# BLE_SCH_Rev1.net
KiCad netlist of a schematic drawn in Altium Designer
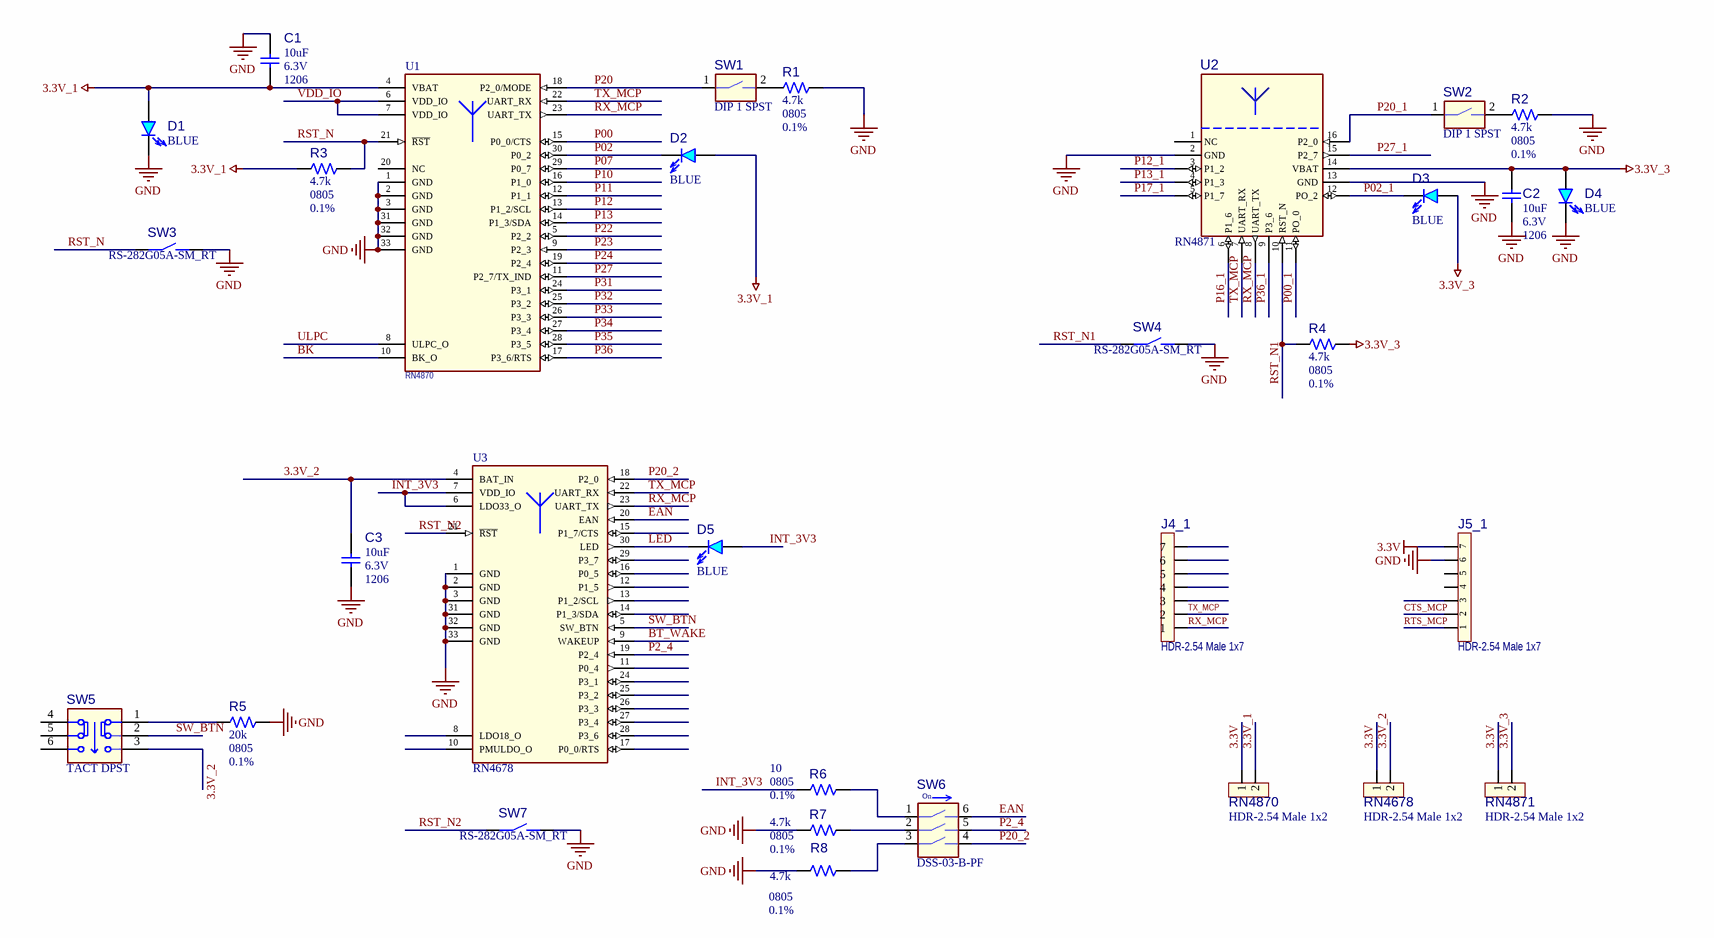
[diagram p0: BLE_SCH_Rev1.SchDoc]

(export (version "E")
  (design (tool "Eeschema 10.0.6"))
  (components
    (comp (ref "C1")
      (value "10uF")
      (footprint "CAP_C_1206")
      (fields
        (field (name "VOLTAGE") "6.3V")
        (field (name "PACKAGE") "1206")
        (field (name "TOLERANCE") "20%")
        (field (name "Comment") "Capacitor NP")
      )
      (libsource (lib "MCHP-CDB") (part "Capacitor NP"))
    )
    (comp (ref "C2")
      (value "10uF")
      (footprint "CAP_C_1206")
      (fields
        (field (name "VOLTAGE") "6.3V")
        (field (name "PACKAGE") "1206")
        (field (name "TOLERANCE") "20%")
        (field (name "Comment") "Capacitor NP")
      )
      (libsource (lib "MCHP-CDB") (part "Capacitor NP"))
    )
    (comp (ref "C3")
      (value "10uF")
      (footprint "CAP_C_1206")
      (fields
        (field (name "VOLTAGE") "6.3V")
        (field (name "PACKAGE") "1206")
        (field (name "TOLERANCE") "20%")
        (field (name "Comment") "Capacitor NP")
      )
      (libsource (lib "MCHP-CDB") (part "Capacitor NP"))
    )
    (comp (ref "D1")
      (value "BLUE")
      (footprint "LED_0805_BLUE")
      (description "LED")
      (fields (field (name "Comment") "LED_blue"))
      (libsource (lib "MCHP-CDB") (part "LED_blue"))
    )
    (comp (ref "D2")
      (value "BLUE")
      (footprint "LED_0805_BLUE")
      (description "LED")
      (fields (field (name "Comment") "LED_blue"))
      (libsource (lib "MCHP-CDB") (part "LED_blue"))
    )
    (comp (ref "D3")
      (value "BLUE")
      (footprint "LED_0805_BLUE")
      (description "LED")
      (fields (field (name "Comment") "LED_blue"))
      (libsource (lib "MCHP-CDB") (part "LED_blue"))
    )
    (comp (ref "D4")
      (value "BLUE")
      (footprint "LED_0805_BLUE")
      (description "LED")
      (fields (field (name "Comment") "LED_blue"))
      (libsource (lib "MCHP-CDB") (part "LED_blue"))
    )
    (comp (ref "D5")
      (value "BLUE")
      (footprint "LED_0805_BLUE")
      (description "LED")
      (fields (field (name "Comment") "LED_blue"))
      (libsource (lib "MCHP-CDB") (part "LED_blue"))
    )
    (comp (ref "J4_1")
      (value "HDR-2.54 Male 1x7")
      (footprint "HDR_M_2.54_1x7")
      (fields (field (name "Comment") "Header 1x7"))
      (libsource (lib "MCHP-CDB") (part "Header 1x7"))
    )
    (comp (ref "J5_1")
      (value "HDR-2.54 Male 1x7")
      (footprint "HDR_M_2.54_1x7")
      (fields (field (name "Comment") "Header 1x7"))
      (libsource (lib "") (part "Header 1x7_1"))
    )
    (comp (ref "R1")
      (value "4.7k")
      (footprint "RES_C_0805")
      (description "Resistor")
      (fields (field (name "PACKAGE") "0805") (field (name "TOLERANCE") "0.1%"))
      (libsource (lib "MCHP-CDB") (part "Resistor"))
    )
    (comp (ref "R2")
      (value "4.7k")
      (footprint "RES_C_0805")
      (description "Resistor")
      (fields (field (name "PACKAGE") "0805") (field (name "TOLERANCE") "0.1%"))
      (libsource (lib "MCHP-CDB") (part "Resistor"))
    )
    (comp (ref "R3")
      (value "4.7k")
      (footprint "RES_C_0805")
      (description "Resistor")
      (fields (field (name "PACKAGE") "0805") (field (name "TOLERANCE") "0.1%"))
      (libsource (lib "MCHP-CDB") (part "Resistor"))
    )
    (comp (ref "R4")
      (value "4.7k")
      (footprint "RES_C_0805")
      (description "Resistor")
      (fields (field (name "PACKAGE") "0805") (field (name "TOLERANCE") "0.1%"))
      (libsource (lib "MCHP-CDB") (part "Resistor"))
    )
    (comp (ref "R5")
      (value "20k")
      (footprint "RES_C_0805")
      (description "Resistor")
      (fields (field (name "PACKAGE") "0805") (field (name "TOLERANCE") "0.1%"))
      (libsource (lib "MCHP-CDB") (part "Resistor"))
    )
    (comp (ref "R6")
      (value "10")
      (footprint "RES_C_0805")
      (description "Resistor")
      (fields (field (name "PACKAGE") "0805") (field (name "TOLERANCE") "0.1%"))
      (libsource (lib "MCHP-CDB") (part "Resistor"))
    )
    (comp (ref "R7")
      (value "4.7k")
      (footprint "RES_C_0805")
      (description "Resistor")
      (fields (field (name "PACKAGE") "0805") (field (name "TOLERANCE") "0.1%"))
      (libsource (lib "MCHP-CDB") (part "Resistor"))
    )
    (comp (ref "R8")
      (value "4.7k")
      (footprint "RES_C_0805")
      (description "Resistor")
      (fields (field (name "PACKAGE") "0805") (field (name "TOLERANCE") "0.1%"))
      (libsource (lib "MCHP-CDB") (part "Resistor"))
    )
    (comp (ref "RN4678")
      (value "HDR-2.54 Male 1x2")
      (footprint "HDR_M_2.54_1x2")
      (fields (field (name "Comment") "Header 1x2") (field (name "OWNER") "Randolph Sobrepena"))
      (libsource (lib "MCHP-CDB") (part "Header 1x2"))
    )
    (comp (ref "RN4870")
      (value "HDR-2.54 Male 1x2")
      (footprint "HDR_M_2.54_1x2")
      (fields (field (name "Comment") "Header 1x2") (field (name "OWNER") "Randolph Sobrepena"))
      (libsource (lib "MCHP-CDB") (part "Header 1x2"))
    )
    (comp (ref "RN4871")
      (value "HDR-2.54 Male 1x2")
      (footprint "HDR_M_2.54_1x2")
      (fields (field (name "Comment") "Header 1x2") (field (name "OWNER") "Randolph Sobrepena"))
      (libsource (lib "MCHP-CDB") (part "Header 1x2"))
    )
    (comp (ref "SW1")
      (value "DIP 1 SPST")
      (footprint "SW_TH_2.54MM X 1 418117270901")
      (description "Switch DIP 1 Pos")
      (fields (field (name "VOLTAGE") "24V") (field (name "OWNER") "Gabor Bihari"))
      (libsource (lib "MCHP-CDB") (part "Switch DIP 1 Pos"))
    )
    (comp (ref "SW2")
      (value "DIP 1 SPST")
      (footprint "SW_TH_2.54MM X 1 418117270901")
      (description "Switch DIP 1 Pos")
      (fields (field (name "VOLTAGE") "24V") (field (name "OWNER") "Gabor Bihari"))
      (libsource (lib "MCHP-CDB") (part "Switch DIP 1 Pos"))
    )
    (comp (ref "SW3")
      (value "RS-282G05A-SM_RT")
      (footprint "SW_TACT_SMD_CK_RS-282G05A3-SM RT")
      (description "Switch")
      (fields
        (field (name "VOLTAGE") "12V")
        (field (name "Comment") "Switch 2 Pin")
        (field (name "OWNER") "Gabor Bihari")
      )
      (libsource (lib "MCHP-CDB") (part "Switch 2 Pin"))
    )
    (comp (ref "SW4")
      (value "RS-282G05A-SM_RT")
      (footprint "SW_TACT_SMD_CK_RS-282G05A3-SM RT")
      (description "Switch")
      (fields
        (field (name "VOLTAGE") "12V")
        (field (name "Comment") "Switch 2 Pin")
        (field (name "OWNER") "Gabor Bihari")
      )
      (libsource (lib "MCHP-CDB") (part "Switch 2 Pin"))
    )
    (comp (ref "SW5")
      (value "TACT DPST")
      (footprint "SW_TACT_TH_PS07-22L-PF")
      (description "PS-5177")
      (fields (field (name "Comment") "Switch on-off 6 Pin") (field (name "OWNER") "Duane Burt"))
      (libsource (lib "MCHP-CDB") (part "Switch on-off 6 Pin"))
    )
    (comp (ref "SW6")
      (value "DSS-03-B-PF")
      (footprint "SW_TH_2.54MM X 3 Omron")
      (description "Switch DIP")
      (fields (field (name "Comment") "Switch DIP 3 Pos") (field (name "OWNER") "Duane Burt"))
      (libsource (lib "MCHP-CDB") (part "Switch DIP 3 Pos"))
    )
    (comp (ref "SW7")
      (value "RS-282G05A-SM_RT")
      (footprint "SW_TACT_SMD_CK_RS-282G05A3-SM RT")
      (description "Switch")
      (fields
        (field (name "VOLTAGE") "12V")
        (field (name "Comment") "Switch 2 Pin")
        (field (name "OWNER") "Gabor Bihari")
      )
      (libsource (lib "MCHP-CDB") (part "Switch 2 Pin"))
    )
    (comp (ref "U1")
      (value "RN4870")
      (footprint "MOD_BM70BLES1FC2")
      (fields (field (name "Comment") "MODULE BM70BLES1FC2") (field (name "OWNER") "Jojie Batislaon"))
      (libsource (lib "MCHP-CDB") (part "MODULE BM70BLES1FC2"))
    )
    (comp (ref "U2")
      (value "RN4871")
      (footprint "RN4871 MODULE-16")
      (fields (field (name "Comment") "RN4871 MODULE") (field (name "OWNER") "Octavian Stroe"))
      (libsource (lib "MCHP-CDB") (part "RN4871 MODULE"))
    )
    (comp (ref "U3")
      (value "RN4678")
      (footprint "MOD_BM78SPPS5xC2")
      (fields (field (name "Comment") "MODULE BM78SPPS5xC2") (field (name "OWNER") "Jojie Batislaon"))
      (libsource (lib "MCHP-CDB") (part "MODULE BM78SPPS5xC2"))
    )
  )
  (nets
    (net (code "1") (name "/3.3V_2") (class "Default")
      (node (ref "C3") (pin "2") (pinfunction "2_2") (pintype "passive"))
      (node (ref "RN4678") (pin "2") (pinfunction "2_2") (pintype "passive"))
      (node (ref "SW5") (pin "3") (pinfunction "3_3") (pintype "passive"))
      (node (ref "U3") (pin "4") (pinfunction "BAT_IN_4") (pintype "power_in"))
    )
    (net (code "2") (name "/BK") (class "Default")
      (node (ref "U1") (pin "10") (pinfunction "BK_O_10") (pintype "passive"))
    )
    (net (code "3") (name "/BT_WAKE") (class "Default")
      (node (ref "U3") (pin "9") (pinfunction "WAKEUP_9") (pintype "input"))
    )
    (net (code "4") (name "/CTS_MCP") (class "Default")
      (node (ref "J5_1") (pin "2") (pinfunction "2_2") (pintype "passive"))
    )
    (net (code "5") (name "/EAN") (class "Default")
      (node (ref "SW6") (pin "6") (pinfunction "6_6") (pintype "passive"))
      (node (ref "U3") (pin "20") (pinfunction "EAN_20") (pintype "input"))
    )
    (net (code "6") (name "/INT_3V3") (class "Default")
      (node (ref "D5") (pin "1") (pinfunction "A_1") (pintype "passive"))
      (node (ref "R6") (pin "2") (pinfunction "2_2") (pintype "passive"))
      (node (ref "U3") (pin "6") (pinfunction "LDO33_O_6") (pintype "power_in"))
      (node (ref "U3") (pin "7") (pinfunction "VDD_IO_7") (pintype "power_in"))
    )
    (net (code "7") (name "/LED") (class "Default")
      (node (ref "D5") (pin "2") (pinfunction "K_2") (pintype "passive"))
      (node (ref "U3") (pin "30") (pinfunction "LED_30") (pintype "output"))
    )
    (net (code "8") (name "/P00") (class "Default")
      (node (ref "U1") (pin "15") (pinfunction "P0_0/CTS_15") (pintype "bidirectional"))
    )
    (net (code "9") (name "/P00_1") (class "Default")
      (node (ref "U2") (pin "11") (pinfunction "PO_0_11") (pintype "bidirectional"))
    )
    (net (code "10") (name "/P02") (class "Default")
      (node (ref "D2") (pin "2") (pinfunction "K_2") (pintype "passive"))
      (node (ref "U1") (pin "30") (pinfunction "P0_2_30") (pintype "bidirectional"))
    )
    (net (code "11") (name "/P02_1") (class "Default")
      (node (ref "D3") (pin "2") (pinfunction "K_2") (pintype "passive"))
      (node (ref "U2") (pin "12") (pinfunction "PO_2_12") (pintype "bidirectional"))
    )
    (net (code "12") (name "/P2_4") (class "Default")
      (node (ref "SW6") (pin "5") (pinfunction "5_5") (pintype "passive"))
      (node (ref "U3") (pin "19") (pinfunction "P2_4_19") (pintype "input"))
    )
    (net (code "13") (name "/P07") (class "Default")
      (node (ref "U1") (pin "29") (pinfunction "P0_7_29") (pintype "bidirectional"))
    )
    (net (code "14") (name "/P10") (class "Default")
      (node (ref "U1") (pin "16") (pinfunction "P1_0_16") (pintype "bidirectional"))
    )
    (net (code "15") (name "/P11") (class "Default")
      (node (ref "U1") (pin "12") (pinfunction "P1_1_12") (pintype "bidirectional"))
    )
    (net (code "16") (name "/P12") (class "Default")
      (node (ref "U1") (pin "13") (pinfunction "P1_2/SCL_13") (pintype "bidirectional"))
    )
    (net (code "17") (name "/P12_1") (class "Default")
      (node (ref "U2") (pin "3") (pinfunction "P1_2_3") (pintype "bidirectional"))
    )
    (net (code "18") (name "/P13") (class "Default")
      (node (ref "U1") (pin "14") (pinfunction "P1_3/SDA_14") (pintype "bidirectional"))
    )
    (net (code "19") (name "/P13_1") (class "Default")
      (node (ref "U2") (pin "4") (pinfunction "P1_3_4") (pintype "bidirectional"))
    )
    (net (code "20") (name "/P16_1") (class "Default")
      (node (ref "U2") (pin "6") (pinfunction "P1_6_6") (pintype "bidirectional"))
    )
    (net (code "21") (name "/P17_1") (class "Default")
      (node (ref "U2") (pin "5") (pinfunction "P1_7_5") (pintype "bidirectional"))
    )
    (net (code "22") (name "/P20") (class "Default")
      (node (ref "SW1") (pin "1") (pinfunction "1_1") (pintype "passive"))
      (node (ref "U1") (pin "18") (pinfunction "P2_0/MODE_18") (pintype "input"))
    )
    (net (code "23") (name "/P20_1") (class "Default")
      (node (ref "SW2") (pin "1") (pinfunction "1_1") (pintype "passive"))
      (node (ref "U2") (pin "16") (pinfunction "P2_0_16") (pintype "input"))
    )
    (net (code "24") (name "/P20_2") (class "Default")
      (node (ref "SW6") (pin "4") (pinfunction "4_4") (pintype "passive"))
      (node (ref "U3") (pin "18") (pinfunction "P2_0_18") (pintype "input"))
    )
    (net (code "25") (name "/P22") (class "Default")
      (node (ref "U1") (pin "5") (pinfunction "P2_2_5") (pintype "bidirectional"))
    )
    (net (code "26") (name "/P23") (class "Default")
      (node (ref "U1") (pin "9") (pinfunction "P2_3_9") (pintype "input"))
    )
    (net (code "27") (name "/P24") (class "Default")
      (node (ref "U1") (pin "19") (pinfunction "P2_4_19") (pintype "bidirectional"))
    )
    (net (code "28") (name "/P27") (class "Default")
      (node (ref "U1") (pin "11") (pinfunction "P2_7/TX_IND_11") (pintype "bidirectional"))
    )
    (net (code "29") (name "/P27_1") (class "Default")
      (node (ref "U2") (pin "15") (pinfunction "P2_7_15") (pintype "output"))
    )
    (net (code "30") (name "/P31") (class "Default")
      (node (ref "U1") (pin "24") (pinfunction "P3_1_24") (pintype "bidirectional"))
    )
    (net (code "31") (name "/P32") (class "Default")
      (node (ref "U1") (pin "25") (pinfunction "P3_2_25") (pintype "bidirectional"))
    )
    (net (code "32") (name "/P33") (class "Default")
      (node (ref "U1") (pin "26") (pinfunction "P3_3_26") (pintype "bidirectional"))
    )
    (net (code "33") (name "/P34") (class "Default")
      (node (ref "U1") (pin "27") (pinfunction "P3_4_27") (pintype "bidirectional"))
    )
    (net (code "34") (name "/P35") (class "Default")
      (node (ref "U1") (pin "28") (pinfunction "P3_5_28") (pintype "bidirectional"))
    )
    (net (code "35") (name "/P36") (class "Default")
      (node (ref "U1") (pin "17") (pinfunction "P3_6/RTS_17") (pintype "bidirectional"))
    )
    (net (code "36") (name "/P36_1") (class "Default")
      (node (ref "U2") (pin "9") (pinfunction "P3_6_9") (pintype "power_in"))
    )
    (net (code "37") (name "/RST_N") (class "Default")
      (node (ref "R3") (pin "1") (pinfunction "1_1") (pintype "passive"))
      (node (ref "SW3") (pin "1") (pinfunction "1_1") (pintype "passive"))
      (node (ref "U1") (pin "21") (pinfunction "~{RST}_21") (pintype "input"))
    )
    (net (code "38") (name "/RST_N1") (class "Default")
      (node (ref "R4") (pin "2") (pinfunction "2_2") (pintype "passive"))
      (node (ref "SW4") (pin "1") (pinfunction "1_1") (pintype "passive"))
      (node (ref "U2") (pin "10") (pinfunction "RST_N_10") (pintype "input"))
    )
    (net (code "39") (name "/RST_N2") (class "Default")
      (node (ref "SW7") (pin "1") (pinfunction "1_1") (pintype "passive"))
      (node (ref "U3") (pin "21") (pinfunction "~{RST}_21") (pintype "input"))
    )
    (net (code "40") (name "/RTS_MCP") (class "Default")
      (node (ref "J5_1") (pin "1") (pinfunction "1_1") (pintype "passive"))
    )
    (net (code "41") (name "/RX_MCP") (class "Default")
      (node (ref "J4_1") (pin "1") (pinfunction "1_1") (pintype "passive"))
      (node (ref "U1") (pin "23") (pinfunction "UART_TX_23") (pintype "output"))
      (node (ref "U2") (pin "8") (pinfunction "UART_TX_8") (pintype "output"))
      (node (ref "U3") (pin "23") (pinfunction "UART_TX_23") (pintype "output"))
    )
    (net (code "42") (name "/SW_BTN") (class "Default")
      (node (ref "SW5") (pin "2") (pinfunction "2_2") (pintype "passive"))
      (node (ref "U3") (pin "5") (pinfunction "SW_BTN_5") (pintype "input"))
    )
    (net (code "43") (name "/TX_MCP") (class "Default")
      (node (ref "J4_1") (pin "2") (pinfunction "2_2") (pintype "passive"))
      (node (ref "U1") (pin "22") (pinfunction "UART_RX_22") (pintype "input"))
      (node (ref "U2") (pin "7") (pinfunction "UART_RX_7") (pintype "input"))
      (node (ref "U3") (pin "22") (pinfunction "UART_RX_22") (pintype "input"))
    )
    (net (code "44") (name "/ULPC") (class "Default")
      (node (ref "U1") (pin "8") (pinfunction "ULPC_O_8") (pintype "passive"))
    )
    (net (code "45") (name "/VDD_IO") (class "Default")
      (node (ref "U1") (pin "6") (pinfunction "VDD_IO_6") (pintype "power_in"))
      (node (ref "U1") (pin "7") (pinfunction "VDD_IO_7") (pintype "power_in"))
    )
    (net (code "46") (name "3.3V") (class "Default")
      (node (ref "J5_1") (pin "7") (pinfunction "7_7") (pintype "passive"))
      (node (ref "RN4678") (pin "1") (pinfunction "1_1") (pintype "passive"))
      (node (ref "RN4870") (pin "1") (pinfunction "1_1") (pintype "passive"))
      (node (ref "RN4871") (pin "1") (pinfunction "1_1") (pintype "passive"))
    )
    (net (code "47") (name "3.3V_1") (class "Default")
      (node (ref "C1") (pin "1") (pinfunction "1_1") (pintype "passive"))
      (node (ref "D1") (pin "1") (pinfunction "A_1") (pintype "passive"))
      (node (ref "D2") (pin "1") (pinfunction "A_1") (pintype "passive"))
      (node (ref "R3") (pin "2") (pinfunction "2_2") (pintype "passive"))
      (node (ref "RN4870") (pin "2") (pinfunction "2_2") (pintype "passive"))
      (node (ref "U1") (pin "4") (pinfunction "VBAT_4") (pintype "power_in"))
    )
    (net (code "48") (name "3.3V_3") (class "Default")
      (node (ref "C2") (pin "1") (pinfunction "1_1") (pintype "passive"))
      (node (ref "D3") (pin "1") (pinfunction "A_1") (pintype "passive"))
      (node (ref "D4") (pin "1") (pinfunction "A_1") (pintype "passive"))
      (node (ref "R4") (pin "1") (pinfunction "1_1") (pintype "passive"))
      (node (ref "RN4871") (pin "2") (pinfunction "2_2") (pintype "passive"))
      (node (ref "U2") (pin "14") (pinfunction "VBAT_14") (pintype "power_in"))
    )
    (net (code "49") (name "GND") (class "Default")
      (node (ref "C1") (pin "2") (pinfunction "2_2") (pintype "passive"))
      (node (ref "C2") (pin "2") (pinfunction "2_2") (pintype "passive"))
      (node (ref "C3") (pin "1") (pinfunction "1_1") (pintype "passive"))
      (node (ref "D1") (pin "2") (pinfunction "K_2") (pintype "passive"))
      (node (ref "D4") (pin "2") (pinfunction "K_2") (pintype "passive"))
      (node (ref "J5_1") (pin "6") (pinfunction "6_6") (pintype "passive"))
      (node (ref "R1") (pin "1") (pinfunction "1_1") (pintype "passive"))
      (node (ref "R2") (pin "1") (pinfunction "1_1") (pintype "passive"))
      (node (ref "R5") (pin "1") (pinfunction "1_1") (pintype "passive"))
      (node (ref "R7") (pin "2") (pinfunction "2_2") (pintype "passive"))
      (node (ref "R8") (pin "2") (pinfunction "2_2") (pintype "passive"))
      (node (ref "SW3") (pin "2") (pinfunction "2_2") (pintype "passive"))
      (node (ref "SW4") (pin "2") (pinfunction "2_2") (pintype "passive"))
      (node (ref "SW7") (pin "2") (pinfunction "2_2") (pintype "passive"))
      (node (ref "U1") (pin "1") (pinfunction "GND_1") (pintype "power_in"))
      (node (ref "U1") (pin "2") (pinfunction "GND_2") (pintype "power_in"))
      (node (ref "U1") (pin "3") (pinfunction "GND_3") (pintype "power_in"))
      (node (ref "U1") (pin "31") (pinfunction "GND_31") (pintype "power_in"))
      (node (ref "U1") (pin "32") (pinfunction "GND_32") (pintype "power_in"))
      (node (ref "U1") (pin "33") (pinfunction "GND_33") (pintype "power_in"))
      (node (ref "U2") (pin "13") (pinfunction "GND_13") (pintype "power_in"))
      (node (ref "U2") (pin "2") (pinfunction "GND_2") (pintype "power_in"))
      (node (ref "U3") (pin "1") (pinfunction "GND_1") (pintype "power_in"))
      (node (ref "U3") (pin "2") (pinfunction "GND_2") (pintype "power_in"))
      (node (ref "U3") (pin "3") (pinfunction "GND_3") (pintype "power_in"))
      (node (ref "U3") (pin "31") (pinfunction "GND_31") (pintype "power_in"))
      (node (ref "U3") (pin "32") (pinfunction "GND_32") (pintype "power_in"))
      (node (ref "U3") (pin "33") (pinfunction "GND_33") (pintype "power_in"))
    )
    (net (code "50") (name "Net-(R1-Pad2)") (class "Default")
      (node (ref "R1") (pin "2") (pinfunction "2_2") (pintype "passive"))
      (node (ref "SW1") (pin "2") (pinfunction "2_2") (pintype "passive"))
    )
    (net (code "51") (name "Net-(R2-Pad2)") (class "Default")
      (node (ref "R2") (pin "2") (pinfunction "2_2") (pintype "passive"))
      (node (ref "SW2") (pin "2") (pinfunction "2_2") (pintype "passive"))
    )
    (net (code "52") (name "Net-(R5-Pad2)") (class "Default")
      (node (ref "R5") (pin "2") (pinfunction "2_2") (pintype "passive"))
      (node (ref "SW5") (pin "1") (pinfunction "1_1") (pintype "passive"))
    )
    (net (code "53") (name "Net-(R6-Pad1)") (class "Default")
      (node (ref "R6") (pin "1") (pinfunction "1_1") (pintype "passive"))
      (node (ref "SW6") (pin "1") (pinfunction "1_1") (pintype "passive"))
    )
    (net (code "54") (name "Net-(R7-Pad1)") (class "Default")
      (node (ref "R7") (pin "1") (pinfunction "1_1") (pintype "passive"))
      (node (ref "SW6") (pin "2") (pinfunction "2_2") (pintype "passive"))
    )
    (net (code "55") (name "Net-(R8-Pad1)") (class "Default")
      (node (ref "R8") (pin "1") (pinfunction "1_1") (pintype "passive"))
      (node (ref "SW6") (pin "3") (pinfunction "3_3") (pintype "passive"))
    )
    (net (code "56") (name "unconnected-(J4_1-Pad3)") (class "Default")
      (node (ref "J4_1") (pin "3") (pinfunction "3_3") (pintype "passive"))
    )
    (net (code "57") (name "unconnected-(J4_1-Pad4)") (class "Default")
      (node (ref "J4_1") (pin "4") (pinfunction "4_4") (pintype "passive"))
    )
    (net (code "58") (name "unconnected-(J4_1-Pad5)") (class "Default")
      (node (ref "J4_1") (pin "5") (pinfunction "5_5") (pintype "passive"))
    )
    (net (code "59") (name "unconnected-(J4_1-Pad6)") (class "Default")
      (node (ref "J4_1") (pin "6") (pinfunction "6_6") (pintype "passive"))
    )
    (net (code "60") (name "unconnected-(J4_1-Pad7)") (class "Default")
      (node (ref "J4_1") (pin "7") (pinfunction "7_7") (pintype "passive"))
    )
    (net (code "61") (name "unconnected-(J5_1-Pad3)") (class "Default")
      (node (ref "J5_1") (pin "3") (pinfunction "3_3") (pintype "passive"))
    )
    (net (code "62") (name "unconnected-(J5_1-Pad4)") (class "Default")
      (node (ref "J5_1") (pin "4") (pinfunction "4_4") (pintype "passive"))
    )
    (net (code "63") (name "unconnected-(J5_1-Pad5)") (class "Default")
      (node (ref "J5_1") (pin "5") (pinfunction "5_5") (pintype "passive"))
    )
    (net (code "64") (name "unconnected-(SW5-Pad4)") (class "Default")
      (node (ref "SW5") (pin "4") (pinfunction "4_4") (pintype "passive"))
    )
    (net (code "65") (name "unconnected-(SW5-Pad5)") (class "Default")
      (node (ref "SW5") (pin "5") (pinfunction "5_5") (pintype "passive"))
    )
    (net (code "66") (name "unconnected-(SW5-Pad6)") (class "Default")
      (node (ref "SW5") (pin "6") (pinfunction "6_6") (pintype "passive"))
    )
    (net (code "67") (name "unconnected-(U1-NC-Pad20)") (class "Default")
      (node (ref "U1") (pin "20") (pinfunction "NC_20") (pintype "passive"))
    )
    (net (code "68") (name "unconnected-(U2-NC-Pad1)") (class "Default")
      (node (ref "U2") (pin "1") (pinfunction "NC_1") (pintype "passive"))
    )
    (net (code "69") (name "unconnected-(U3-LDO18_O-Pad8)") (class "Default")
      (node (ref "U3") (pin "8") (pinfunction "LDO18_O_8") (pintype "passive"))
    )
    (net (code "70") (name "unconnected-(U3-P0_0{slash}RTS-Pad17)") (class "Default")
      (node (ref "U3") (pin "17") (pinfunction "P0_0/RTS_17") (pintype "bidirectional"))
    )
    (net (code "71") (name "unconnected-(U3-P0_4-Pad11)") (class "Default")
      (node (ref "U3") (pin "11") (pinfunction "P0_4_11") (pintype "output"))
    )
    (net (code "72") (name "unconnected-(U3-P0_5-Pad16)") (class "Default")
      (node (ref "U3") (pin "16") (pinfunction "P0_5_16") (pintype "bidirectional"))
    )
    (net (code "73") (name "unconnected-(U3-P1_2{slash}SCL-Pad13)") (class "Default")
      (node (ref "U3") (pin "13") (pinfunction "P1_2/SCL_13") (pintype "output"))
    )
    (net (code "74") (name "unconnected-(U3-P1_3{slash}SDA-Pad14)") (class "Default")
      (node (ref "U3") (pin "14") (pinfunction "P1_3/SDA_14") (pintype "bidirectional"))
    )
    (net (code "75") (name "unconnected-(U3-P1_5-Pad12)") (class "Default")
      (node (ref "U3") (pin "12") (pinfunction "P1_5_12") (pintype "output"))
    )
    (net (code "76") (name "unconnected-(U3-P1_7{slash}CTS-Pad15)") (class "Default")
      (node (ref "U3") (pin "15") (pinfunction "P1_7/CTS_15") (pintype "bidirectional"))
    )
    (net (code "77") (name "unconnected-(U3-P3_1-Pad24)") (class "Default")
      (node (ref "U3") (pin "24") (pinfunction "P3_1_24") (pintype "bidirectional"))
    )
    (net (code "78") (name "unconnected-(U3-P3_2-Pad25)") (class "Default")
      (node (ref "U3") (pin "25") (pinfunction "P3_2_25") (pintype "bidirectional"))
    )
    (net (code "79") (name "unconnected-(U3-P3_3-Pad26)") (class "Default")
      (node (ref "U3") (pin "26") (pinfunction "P3_3_26") (pintype "bidirectional"))
    )
    (net (code "80") (name "unconnected-(U3-P3_4-Pad27)") (class "Default")
      (node (ref "U3") (pin "27") (pinfunction "P3_4_27") (pintype "bidirectional"))
    )
    (net (code "81") (name "unconnected-(U3-P3_6-Pad28)") (class "Default")
      (node (ref "U3") (pin "28") (pinfunction "P3_6_28") (pintype "bidirectional"))
    )
    (net (code "82") (name "unconnected-(U3-P3_7-Pad29)") (class "Default")
      (node (ref "U3") (pin "29") (pinfunction "P3_7_29") (pintype "bidirectional"))
    )
    (net (code "83") (name "unconnected-(U3-PMULDO_O-Pad10)") (class "Default")
      (node (ref "U3") (pin "10") (pinfunction "PMULDO_O_10") (pintype "passive"))
    )
  )
)
